# ADCwHarness.net
KiCad netlist of a schematic drawn in Altium Designer
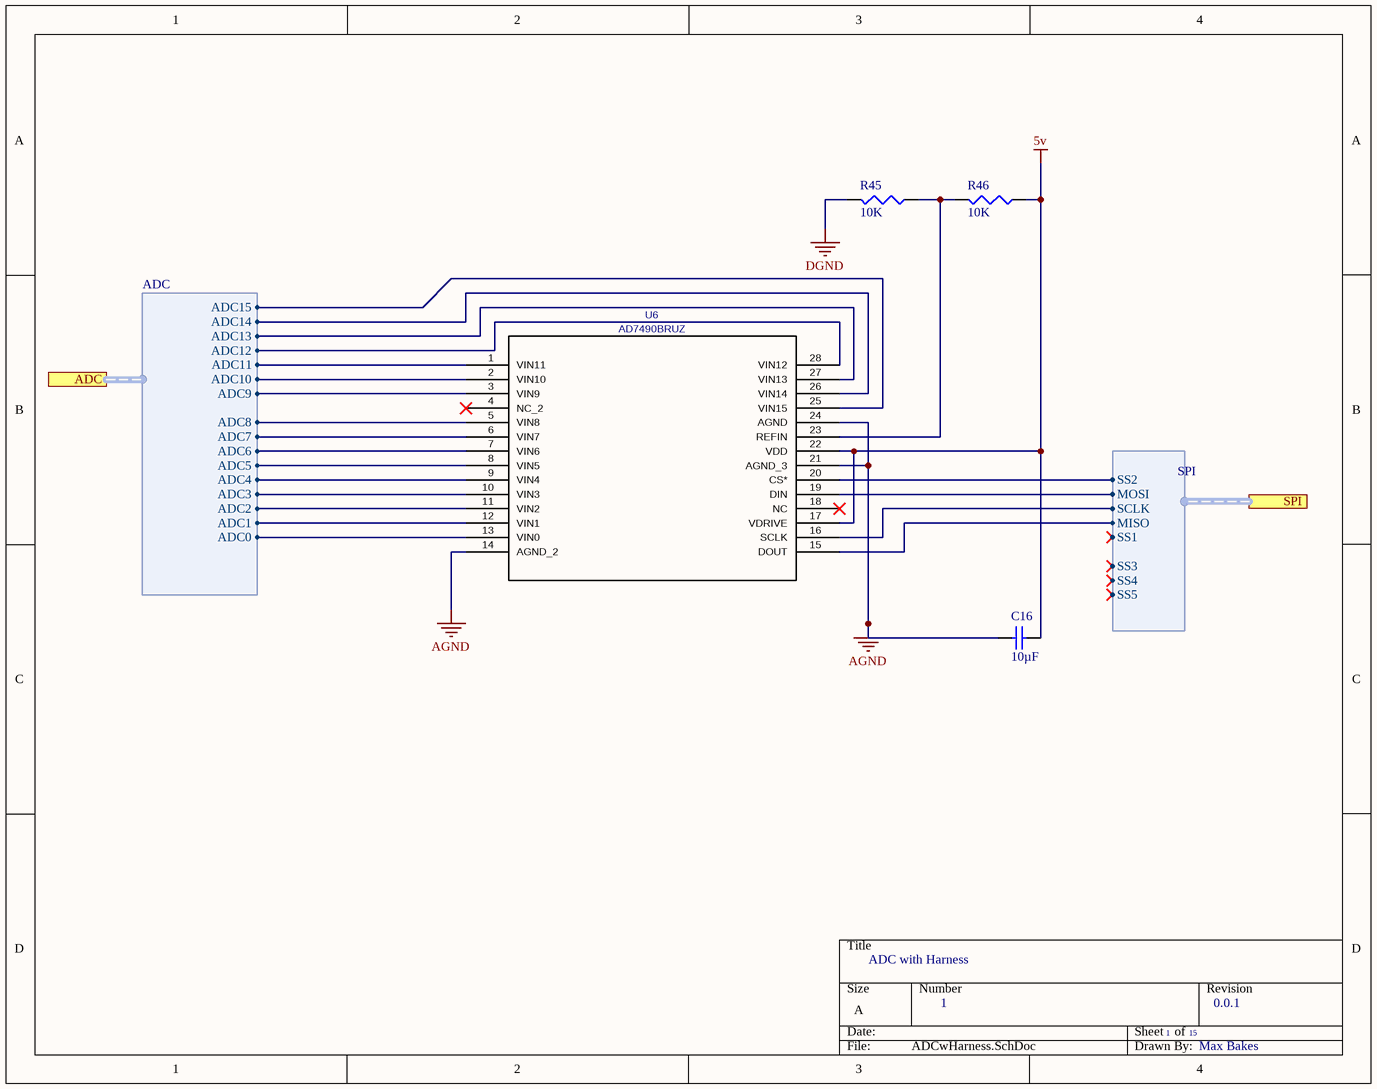
[diagram p0: ADCwHarness.SchDoc]

(export (version "E")
  (design (tool "Eeschema 10.0.6"))
  (components
    (comp (ref "C16")
      (value "C1608X5R1A106K080AC")
      (footprint "CAPC1608X90X20LL10")
      (description "Chip Capacitor, 10 uF, +/- 10%, 10 V, -55 to 85 degC, 0603 (1608 Metric), RoHS, Tape and Reel")
      (fields
        (field (name "PCN PART NUMBER") "MLCCPartNumberChange30/Nov/2012")
        (field (name "TOLERANCE") "±10%")
        (field (name "CAPACITANCE") "10µF")
      )
      (libsource (lib "Passives") (part "CMP-2000-04979-1"))
    )
    (comp (ref "R45")
      (value "10K")
      (footprint "J1-0603")
      (description "Resistor")
      (fields (field (name "Comment") "Res3") (field (name "PUBLISHER") "Altium Limited"))
      (libsource (lib "Miscellaneous Devices") (part "Res3"))
    )
    (comp (ref "R46")
      (value "10K")
      (footprint "J1-0603")
      (description "Resistor")
      (fields (field (name "Comment") "Res3") (field (name "PUBLISHER") "Altium Limited"))
      (libsource (lib "Miscellaneous Devices") (part "Res3"))
    )
    (comp (ref "U6")
      (value "AD7490BRUZ")
      (footprint "*SOP65P640X120-28N")
      (description "16-Channel, 1 MSPS, 12-Bit ADC\r\nwith Sequencer in 28-Lead TSSOP")
      (libsource (lib "2020-02-18_20-13-48") (part "AD7490BRUZ"))
    )
  )
  (nets
    (net (code "3") (name "/ADC0") (class "Default")
      (node (ref "U6") (pin "13") (pinfunction "VIN0_13") (pintype "passive"))
    )
    (net (code "4") (name "/ADC1") (class "Default")
      (node (ref "U6") (pin "12") (pinfunction "VIN1_12") (pintype "passive"))
    )
    (net (code "5") (name "/ADC2") (class "Default")
      (node (ref "U6") (pin "11") (pinfunction "VIN2_11") (pintype "passive"))
    )
    (net (code "6") (name "/ADC3") (class "Default")
      (node (ref "U6") (pin "10") (pinfunction "VIN3_10") (pintype "passive"))
    )
    (net (code "7") (name "/ADC4") (class "Default")
      (node (ref "U6") (pin "9") (pinfunction "VIN4_9") (pintype "passive"))
    )
    (net (code "8") (name "/ADC5") (class "Default")
      (node (ref "U6") (pin "8") (pinfunction "VIN5_8") (pintype "passive"))
    )
    (net (code "9") (name "/ADC6") (class "Default")
      (node (ref "U6") (pin "7") (pinfunction "VIN6_7") (pintype "passive"))
    )
    (net (code "10") (name "/ADC7") (class "Default")
      (node (ref "U6") (pin "6") (pinfunction "VIN7_6") (pintype "passive"))
    )
    (net (code "11") (name "/ADC8") (class "Default")
      (node (ref "U6") (pin "5") (pinfunction "VIN8_5") (pintype "passive"))
    )
    (net (code "12") (name "/ADC9") (class "Default")
      (node (ref "U6") (pin "3") (pinfunction "VIN9_3") (pintype "passive"))
    )
    (net (code "13") (name "/ADC10") (class "Default")
      (node (ref "U6") (pin "2") (pinfunction "VIN10_2") (pintype "passive"))
    )
    (net (code "14") (name "/ADC11") (class "Default")
      (node (ref "U6") (pin "1") (pinfunction "VIN11_1") (pintype "passive"))
    )
    (net (code "15") (name "/ADC12") (class "Default")
      (node (ref "U6") (pin "28") (pinfunction "VIN12_28") (pintype "passive"))
    )
    (net (code "16") (name "/ADC13") (class "Default")
      (node (ref "U6") (pin "27") (pinfunction "VIN13_27") (pintype "passive"))
    )
    (net (code "17") (name "/ADC14") (class "Default")
      (node (ref "U6") (pin "26") (pinfunction "VIN14_26") (pintype "passive"))
    )
    (net (code "18") (name "/ADC15") (class "Default")
      (node (ref "U6") (pin "25") (pinfunction "VIN15_25") (pintype "passive"))
    )
    (net (code "19") (name "/MISO") (class "Default")
      (node (ref "U6") (pin "15") (pinfunction "DOUT_15") (pintype "passive"))
    )
    (net (code "20") (name "/MOSI") (class "Default")
      (node (ref "U6") (pin "19") (pinfunction "DIN_19") (pintype "passive"))
    )
    (net (code "21") (name "/SCLK") (class "Default")
      (node (ref "U6") (pin "16") (pinfunction "SCLK_16") (pintype "passive"))
    )
    (net (code "22") (name "/SS2") (class "Default")
      (node (ref "U6") (pin "20") (pinfunction "CS*_20") (pintype "passive"))
    )
    (net (code "25") (name "5v") (class "Default")
      (node (ref "C16") (pin "2") (pinfunction "2_2") (pintype "passive"))
      (node (ref "R46") (pin "1") (pinfunction "1_1") (pintype "passive"))
      (node (ref "U6") (pin "17") (pinfunction "VDRIVE_17") (pintype "passive"))
      (node (ref "U6") (pin "22") (pinfunction "VDD_22") (pintype "power_in"))
    )
    (net (code "26") (name "AGND") (class "Default")
      (node (ref "C16") (pin "1") (pinfunction "1_1") (pintype "passive"))
      (node (ref "U6") (pin "14") (pinfunction "AGND_2_14") (pintype "passive"))
      (node (ref "U6") (pin "21") (pinfunction "AGND_3_21") (pintype "passive"))
      (node (ref "U6") (pin "24") (pinfunction "AGND_24") (pintype "passive"))
    )
    (net (code "27") (name "DGND") (class "Default")
      (node (ref "R45") (pin "2") (pinfunction "2_2") (pintype "passive"))
    )
    (net (code "28") (name "Net-(U6-REFIN)") (class "Default")
      (node (ref "R45") (pin "1") (pinfunction "1_1") (pintype "passive"))
      (node (ref "R46") (pin "2") (pinfunction "2_2") (pintype "passive"))
      (node (ref "U6") (pin "23") (pinfunction "REFIN_23") (pintype "passive"))
    )
    (net (code "29") (name "unconnected-(U6-NC-Pad18)") (class "Default")
      (node (ref "U6") (pin "18") (pinfunction "NC_18") (pintype "passive+no_connect"))
    )
    (net (code "30") (name "unconnected-(U6-NC_2-Pad4)") (class "Default")
      (node (ref "U6") (pin "4") (pinfunction "NC_2_4") (pintype "passive+no_connect"))
    )
  )
)
